# Modulo_22.net
KiCad netlist of a schematic drawn in Altium Designer
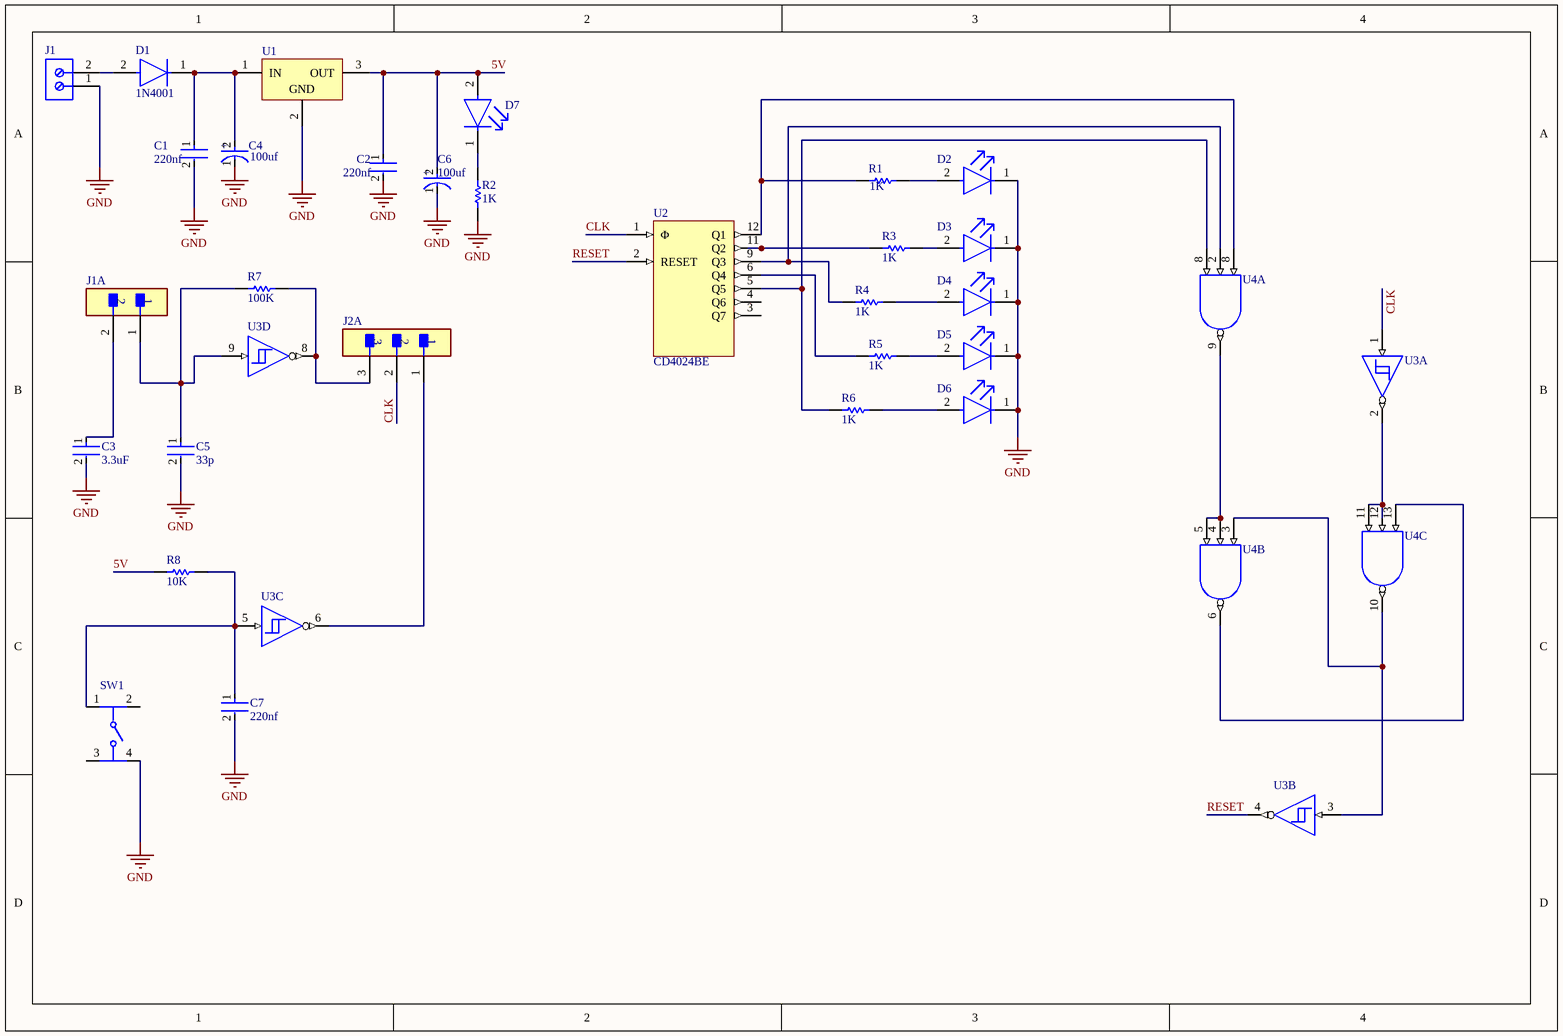
[diagram p0: Modulo_22.SchDoc]

(export (version "E")
  (design (tool "Eeschema 10.0.6"))
  (components
    (comp (ref "C1")
      (value "220nf")
      (footprint "FP-RDE0P1-MFG")
      (description "Ceramic Capacitor 5pF ±0.25pF 50V C0G Radial")
      (libsource (lib "Altium Content Vault") (part "b4654b650e69147ec39a6b967a45e02"))
    )
    (comp (ref "C2")
      (value "220nf")
      (footprint "FP-RDE0P1-MFG")
      (description "Ceramic Capacitor 5pF ±0.25pF 50V C0G Radial")
      (libsource (lib "Altium Content Vault") (part "b4654b650e69147ec39a6b967a45e02"))
    )
    (comp (ref "C3")
      (value "3.3uF")
      (footprint "FP-RDE0P1-MFG")
      (description "Ceramic Capacitor 5pF ±0.25pF 50V C0G Radial")
      (libsource (lib "Altium Content Vault") (part "b4654b650e69147ec39a6b967a45e02"))
    )
    (comp (ref "C4")
      (value "100uf")
      (footprint "FP-RAD-TH-D_6_3_0_5-L_11-MFG")
      (description "Aluminum Electrolytic Capacitors (Radial Lead Type) 100uF ±20% 25V")
      (fields (field (name "TOLERANCE") "20%"))
      (libsource (lib "Altium Content Vault") (part "a00bbbee19879c290e62620ae7e47b1"))
    )
    (comp (ref "C5")
      (value "33p")
      (footprint "FP-RDE0P1-MFG")
      (description "Ceramic Capacitor 5pF ±0.25pF 50V C0G Radial")
      (libsource (lib "Altium Content Vault") (part "b4654b650e69147ec39a6b967a45e02"))
    )
    (comp (ref "C6")
      (value "100uf")
      (footprint "FP-RAD-TH-D_6_3_0_5-L_11-MFG")
      (description "Aluminum Electrolytic Capacitors (Radial Lead Type) 100uF ±20% 25V")
      (fields (field (name "TOLERANCE") "20%"))
      (libsource (lib "Altium Content Vault") (part "a00bbbee19879c290e62620ae7e47b1"))
    )
    (comp (ref "C7")
      (value "220nf")
      (footprint "FP-RDE0P1-MFG")
      (description "Ceramic Capacitor 5pF ±0.25pF 50V C0G Radial")
      (libsource (lib "Altium Content Vault") (part "b4654b650e69147ec39a6b967a45e02"))
    )
    (comp (ref "D1")
      (value "1N4001")
      (footprint "FP-1N4001-E3-73-MFG")
      (description "DIODE GEN PURP 50V 1A DO204AL")
      (fields (field (name "MANUFACTURER PART NUMBER") "1N4001-E3/73") (field (name "MANUFACTURER") "Vishay"))
      (libsource (lib "Altium Content Vault") (part "d7152d700b627762746794eb795d46e"))
    )
    (comp (ref "D2")
      (value "TLLG4400-AS12")
      (footprint "FP-6_544-5255_01-4-MFG")
      (description "LED GREEN DIFFUSED T-1 T/H")
      (libsource (lib "Altium Content Vault") (part "8706943c75ba83719d021d2fdc84c58"))
    )
    (comp (ref "D3")
      (value "TLLG4400-AS12")
      (footprint "FP-6_544-5255_01-4-MFG")
      (description "LED GREEN DIFFUSED T-1 T/H")
      (libsource (lib "Altium Content Vault") (part "8706943c75ba83719d021d2fdc84c58"))
    )
    (comp (ref "D4")
      (value "TLLG4400-AS12")
      (footprint "FP-6_544-5255_01-4-MFG")
      (description "LED GREEN DIFFUSED T-1 T/H")
      (libsource (lib "Altium Content Vault") (part "8706943c75ba83719d021d2fdc84c58"))
    )
    (comp (ref "D5")
      (value "TLLG4400-AS12")
      (footprint "FP-6_544-5255_01-4-MFG")
      (description "LED GREEN DIFFUSED T-1 T/H")
      (libsource (lib "Altium Content Vault") (part "8706943c75ba83719d021d2fdc84c58"))
    )
    (comp (ref "D6")
      (value "TLLG4400-AS12")
      (footprint "FP-6_544-5255_01-4-MFG")
      (description "LED GREEN DIFFUSED T-1 T/H")
      (libsource (lib "Altium Content Vault") (part "8706943c75ba83719d021d2fdc84c58"))
    )
    (comp (ref "D7")
      (value "TLLG4400-AS12")
      (footprint "FP-6_544-5255_01-4-MFG")
      (description "LED GREEN DIFFUSED T-1 T/H")
      (libsource (lib "Altium Content Vault") (part "8706943c75ba83719d021d2fdc84c58"))
    )
    (comp (ref "J1")
      (value "282836-2")
      (footprint "TECO-282836-2_V")
      (description "Female Header, Pitch 5 mm, 1 x 2 Position, Height 10 mm, Tail Length 3.5 mm, Rohs, Bulk")
      (fields (field (name "VOLTAGE") "300V") (field (name "MANUFACTURER") "TE Connectivity"))
      (libsource (lib "Altium Content Vault") (part "CN-1P-F-TB2"))
    )
    (comp (ref "J1A")
      (value "TSW-102-14-G-S")
      (footprint "FP-TSW-102-14-G-S-MFG")
      (description "CONN HEADER VERT 2POS 2.54MM")
      (libsource (lib "Altium Content Vault") (part "88c1139f9d239099ffebecbe3f7647a"))
    )
    (comp (ref "J2A")
      (value "PR20203VBNN")
      (footprint "FP-PR20203VBNN-MFG")
      (description "CONN HEADER VERT 3POS 2.54MM")
      (fields
        (field (name "OCTOPART") "https://octopart.com/pr20203vbnn-metz+connect-87667116")
        (field (name "MANUFACTURER") "Metz Connect")
      )
      (libsource (lib "Altium Content Vault") (part "0d3f023dd272f625e17a2be33dea85f"))
    )
    (comp (ref "R1")
      (value "1K")
      (footprint "RESA60-630X240")
      (description "Axial Resistor, 1 KOhm, +/- 1%, 250 mW, -55 to 155 degC, 2-Pin THD, RoHS, Bulk")
      (fields (field (name "TOLERANCE") "1%"))
      (libsource (lib "Altium Content Vault") (part "RES-2"))
    )
    (comp (ref "R2")
      (value "1K")
      (footprint "RESA60-630X240")
      (description "Axial Resistor, 1 KOhm, +/- 1%, 250 mW, -55 to 155 degC, 2-Pin THD, RoHS, Bulk")
      (fields (field (name "TOLERANCE") "1%"))
      (libsource (lib "Altium Content Vault") (part "RES-2"))
    )
    (comp (ref "R3")
      (value "1K")
      (footprint "RESA60-630X240")
      (description "Axial Resistor, 1 KOhm, +/- 1%, 250 mW, -55 to 155 degC, 2-Pin THD, RoHS, Bulk")
      (fields (field (name "TOLERANCE") "1%"))
      (libsource (lib "Altium Content Vault") (part "RES-2"))
    )
    (comp (ref "R4")
      (value "1K")
      (footprint "RESA60-630X240")
      (description "Axial Resistor, 1 KOhm, +/- 1%, 250 mW, -55 to 155 degC, 2-Pin THD, RoHS, Bulk")
      (fields (field (name "TOLERANCE") "1%"))
      (libsource (lib "Altium Content Vault") (part "RES-2"))
    )
    (comp (ref "R5")
      (value "1K")
      (footprint "RESA60-630X240")
      (description "Axial Resistor, 1 KOhm, +/- 1%, 250 mW, -55 to 155 degC, 2-Pin THD, RoHS, Bulk")
      (fields (field (name "TOLERANCE") "1%"))
      (libsource (lib "Altium Content Vault") (part "RES-2"))
    )
    (comp (ref "R6")
      (value "1K")
      (footprint "RESA60-630X240")
      (description "Axial Resistor, 1 KOhm, +/- 1%, 250 mW, -55 to 155 degC, 2-Pin THD, RoHS, Bulk")
      (fields (field (name "TOLERANCE") "1%"))
      (libsource (lib "Altium Content Vault") (part "RES-2"))
    )
    (comp (ref "R7")
      (value "100K")
      (footprint "RESA60-630X240")
      (description "Axial Resistor, 1 KOhm, +/- 1%, 250 mW, -55 to 155 degC, 2-Pin THD, RoHS, Bulk")
      (fields (field (name "TOLERANCE") "1%"))
      (libsource (lib "") (part "RES-2_1"))
    )
    (comp (ref "R8")
      (value "10K")
      (footprint "RESA60-630X240")
      (description "Axial Resistor, 1 KOhm, +/- 1%, 250 mW, -55 to 155 degC, 2-Pin THD, RoHS, Bulk")
      (fields (field (name "TOLERANCE") "1%"))
      (libsource (lib "") (part "RES-2_1"))
    )
    (comp (ref "SW1")
      (value "TL1105AF160Q")
      (footprint "FP-TL1105AF160Q-MFG")
      (description "SWITCH TACTILE SPST-NO 0.05A 12V")
      (libsource (lib "Altium Content Vault") (part "82b636f13fd696edb7519609c0a8a76"))
    )
    (comp (ref "U1")
      (value "L7805CP")
      (footprint "TO220FP")
      (description "Positive Voltage Regulator, 5V, 3-Pin TO-220FP")
      (libsource (lib "Altium Content Vault") (part "PM-REG-L4940-SIL3"))
    )
    (comp (ref "U2")
      (value "CD4024BE")
      (footprint "N0014A")
      (description "CMOS 7-Stage Ripple-Carry Binary Counter/Divider, N0014A, TUBE")
      (fields
        (field (name "GENERIC PART NUMBER") "CD4024B")
        (field (name "MANUFACTURER") "Texas Instruments")
      )
      (libsource (lib "Altium Content Vault") (part "TI-CD4024B-14"))
    )
    (comp (ref "U3")
      (value "CD40106BE")
      (footprint "N0014A")
      (description "CMOS Hex Schmitt Triggers, N0014A, TUBE")
      (fields
        (field (name "MANUFACTURER") "Texas Instruments")
        (field (name "GENERIC PART NUMBER") "CD40106B")
      )
      (libsource (lib "") (part "TI-CD40XXXB-14-SCHMITT_2"))
    )
    (comp (ref "U4")
      (value "CD4023BF")
      (footprint "J0014A")
      (description "CMOS Triple 3-Input NAND Gate, J0014A, TUBE")
      (fields
        (field (name "MANUFACTURER") "Texas Instruments")
        (field (name "GENERIC PART NUMBER") "CD4023B")
      )
      (libsource (lib "") (part "TI-CD4023B-14_1"))
    )
  )
  (nets
    (net (code "1") (name "/5V") (class "Default")
      (node (ref "C2") (pin "1") (pinfunction "1_1") (pintype "passive"))
      (node (ref "C6") (pin "2") (pinfunction "A_2") (pintype "passive"))
      (node (ref "D7") (pin "2") (pinfunction "A_2") (pintype "passive"))
      (node (ref "R8") (pin "1") (pinfunction "1_1") (pintype "passive"))
      (node (ref "U1") (pin "3") (pinfunction "OUT_3") (pintype "power_in"))
    )
    (net (code "2") (name "/CLK") (class "Default")
      (node (ref "J2A") (pin "2") (pinfunction "2_2") (pintype "passive"))
      (node (ref "U2") (pin "1") (pinfunction "Φ_1") (pintype "input"))
      (node (ref "U3") (pin "1") (pinfunction "A_1") (pintype "input"))
    )
    (net (code "3") (name "/RESET") (class "Default")
      (node (ref "U2") (pin "2") (pinfunction "RESET_2") (pintype "input"))
      (node (ref "U3") (pin "4") (pinfunction "H=~{B}_4") (pintype "output"))
    )
    (net (code "4") (name "GND") (class "Default")
      (node (ref "C1") (pin "2") (pinfunction "2_2") (pintype "passive"))
      (node (ref "C2") (pin "2") (pinfunction "2_2") (pintype "passive"))
      (node (ref "C3") (pin "2") (pinfunction "2_2") (pintype "passive"))
      (node (ref "C4") (pin "1") (pinfunction "C_1") (pintype "passive"))
      (node (ref "C5") (pin "2") (pinfunction "2_2") (pintype "passive"))
      (node (ref "C6") (pin "1") (pinfunction "C_1") (pintype "passive"))
      (node (ref "C7") (pin "2") (pinfunction "2_2") (pintype "passive"))
      (node (ref "D2") (pin "1") (pinfunction "C_1") (pintype "passive"))
      (node (ref "D3") (pin "1") (pinfunction "C_1") (pintype "passive"))
      (node (ref "D4") (pin "1") (pinfunction "C_1") (pintype "passive"))
      (node (ref "D5") (pin "1") (pinfunction "C_1") (pintype "passive"))
      (node (ref "D6") (pin "1") (pinfunction "C_1") (pintype "passive"))
      (node (ref "J1") (pin "1") (pinfunction "1_1") (pintype "passive"))
      (node (ref "R2") (pin "1") (pinfunction "1_1") (pintype "passive"))
      (node (ref "SW1") (pin "4") (pinfunction "4_4") (pintype "passive"))
      (node (ref "U1") (pin "2") (pinfunction "GND_2") (pintype "power_in"))
    )
    (net (code "5") (name "Net-(C3-Pad1)") (class "Default")
      (node (ref "C3") (pin "1") (pinfunction "1_1") (pintype "passive"))
      (node (ref "J1A") (pin "2") (pinfunction "2_2") (pintype "passive"))
    )
    (net (code "6") (name "Net-(C4-A)") (class "Default")
      (node (ref "C1") (pin "1") (pinfunction "1_1") (pintype "passive"))
      (node (ref "C4") (pin "2") (pinfunction "A_2") (pintype "passive"))
      (node (ref "D1") (pin "1") (pinfunction "C_1") (pintype "passive"))
      (node (ref "U1") (pin "1") (pinfunction "IN_1") (pintype "power_in"))
    )
    (net (code "7") (name "Net-(D1-A)") (class "Default")
      (node (ref "D1") (pin "2") (pinfunction "A_2") (pintype "passive"))
      (node (ref "J1") (pin "2") (pinfunction "2_2") (pintype "passive"))
    )
    (net (code "8") (name "Net-(D2-A)") (class "Default")
      (node (ref "D2") (pin "2") (pinfunction "A_2") (pintype "passive"))
      (node (ref "R1") (pin "2") (pinfunction "2_2") (pintype "passive"))
    )
    (net (code "9") (name "Net-(D3-A)") (class "Default")
      (node (ref "D3") (pin "2") (pinfunction "A_2") (pintype "passive"))
      (node (ref "R3") (pin "2") (pinfunction "2_2") (pintype "passive"))
    )
    (net (code "10") (name "Net-(D4-A)") (class "Default")
      (node (ref "D4") (pin "2") (pinfunction "A_2") (pintype "passive"))
      (node (ref "R4") (pin "2") (pinfunction "2_2") (pintype "passive"))
    )
    (net (code "11") (name "Net-(D5-A)") (class "Default")
      (node (ref "D5") (pin "2") (pinfunction "A_2") (pintype "passive"))
      (node (ref "R5") (pin "2") (pinfunction "2_2") (pintype "passive"))
    )
    (net (code "12") (name "Net-(D6-A)") (class "Default")
      (node (ref "D6") (pin "2") (pinfunction "A_2") (pintype "passive"))
      (node (ref "R6") (pin "2") (pinfunction "2_2") (pintype "passive"))
    )
    (net (code "13") (name "Net-(D7-C)") (class "Default")
      (node (ref "D7") (pin "1") (pinfunction "C_1") (pintype "passive"))
      (node (ref "R2") (pin "2") (pinfunction "2_2") (pintype "passive"))
    )
    (net (code "14") (name "Net-(U2-Q1)") (class "Default")
      (node (ref "R1") (pin "1") (pinfunction "1_1") (pintype "passive"))
      (node (ref "U2") (pin "12") (pinfunction "Q1_12") (pintype "output"))
      (node (ref "U4") (pin "8") (pinfunction "C_8") (pintype "input"))
    )
    (net (code "15") (name "Net-(U2-Q2)") (class "Default")
      (node (ref "R3") (pin "1") (pinfunction "1_1") (pintype "passive"))
      (node (ref "U2") (pin "11") (pinfunction "Q2_11") (pintype "output"))
    )
    (net (code "16") (name "Net-(U2-Q3)") (class "Default")
      (node (ref "R4") (pin "1") (pinfunction "1_1") (pintype "passive"))
      (node (ref "U2") (pin "9") (pinfunction "Q3_9") (pintype "output"))
      (node (ref "U4") (pin "2") (pinfunction "B_2") (pintype "input"))
    )
    (net (code "17") (name "Net-(U2-Q4)") (class "Default")
      (node (ref "R5") (pin "1") (pinfunction "1_1") (pintype "passive"))
      (node (ref "U2") (pin "6") (pinfunction "Q4_6") (pintype "output"))
    )
    (net (code "18") (name "Net-(U2-Q5)") (class "Default")
      (node (ref "R6") (pin "1") (pinfunction "1_1") (pintype "passive"))
      (node (ref "U2") (pin "5") (pinfunction "Q5_5") (pintype "output"))
      (node (ref "U4") (pin "8") (pinfunction "C_8") (pintype "input"))
    )
    (net (code "19") (name "Net-(U3A-G=~{A})") (class "Default")
      (node (ref "U3") (pin "2") (pinfunction "G=~{A}_2") (pintype "output"))
      (node (ref "U4") (pin "11") (pinfunction "I_11") (pintype "input"))
      (node (ref "U4") (pin "12") (pinfunction "H_12") (pintype "input"))
    )
    (net (code "20") (name "Net-(U3B-B)") (class "Default")
      (node (ref "U3") (pin "3") (pinfunction "B_3") (pintype "input"))
      (node (ref "U4") (pin "10") (pinfunction "L_10") (pintype "output"))
      (node (ref "U4") (pin "3") (pinfunction "D_3") (pintype "input"))
    )
    (net (code "21") (name "Net-(U3C-C)") (class "Default")
      (node (ref "C7") (pin "1") (pinfunction "1_1") (pintype "passive"))
      (node (ref "R8") (pin "2") (pinfunction "2_2") (pintype "passive"))
      (node (ref "SW1") (pin "1") (pinfunction "1_1") (pintype "passive"))
      (node (ref "U3") (pin "5") (pinfunction "C_5") (pintype "input"))
    )
    (net (code "22") (name "Net-(U3C-I=~{C})") (class "Default")
      (node (ref "J2A") (pin "1") (pinfunction "1_1") (pintype "passive"))
      (node (ref "U3") (pin "6") (pinfunction "I=~{C}_6") (pintype "output"))
    )
    (net (code "23") (name "Net-(U3D-D)") (class "Default")
      (node (ref "C5") (pin "1") (pinfunction "1_1") (pintype "passive"))
      (node (ref "J1A") (pin "1") (pinfunction "1_1") (pintype "passive"))
      (node (ref "R7") (pin "1") (pinfunction "1_1") (pintype "passive"))
      (node (ref "U3") (pin "9") (pinfunction "D_9") (pintype "input"))
    )
    (net (code "24") (name "Net-(U3D-J=~{D})") (class "Default")
      (node (ref "J2A") (pin "3") (pinfunction "3_3") (pintype "passive"))
      (node (ref "R7") (pin "2") (pinfunction "2_2") (pintype "passive"))
      (node (ref "U3") (pin "8") (pinfunction "J=~{D}_8") (pintype "output"))
    )
    (net (code "25") (name "Net-(U4A-J)") (class "Default")
      (node (ref "U4") (pin "4") (pinfunction "E_4") (pintype "input"))
      (node (ref "U4") (pin "5") (pinfunction "F_5") (pintype "input"))
      (node (ref "U4") (pin "9") (pinfunction "J_9") (pintype "output"))
    )
    (net (code "26") (name "Net-(U4B-K)") (class "Default")
      (node (ref "U4") (pin "13") (pinfunction "G_13") (pintype "input"))
      (node (ref "U4") (pin "6") (pinfunction "K_6") (pintype "output"))
    )
    (net (code "27") (name "unconnected-(SW1-Pad2)") (class "Default")
      (node (ref "SW1") (pin "2") (pinfunction "2_2") (pintype "passive"))
    )
    (net (code "28") (name "unconnected-(SW1-Pad3)") (class "Default")
      (node (ref "SW1") (pin "3") (pinfunction "3_3") (pintype "passive"))
    )
    (net (code "29") (name "unconnected-(U2-Q6-Pad4)") (class "Default")
      (node (ref "U2") (pin "4") (pinfunction "Q6_4") (pintype "output"))
    )
    (net (code "30") (name "unconnected-(U2-Q7-Pad3)") (class "Default")
      (node (ref "U2") (pin "3") (pinfunction "Q7_3") (pintype "output"))
    )
  )
)
